# ledtiny85-nrf-sot23.net
KiCad netlist of a schematic drawn in EAGLE
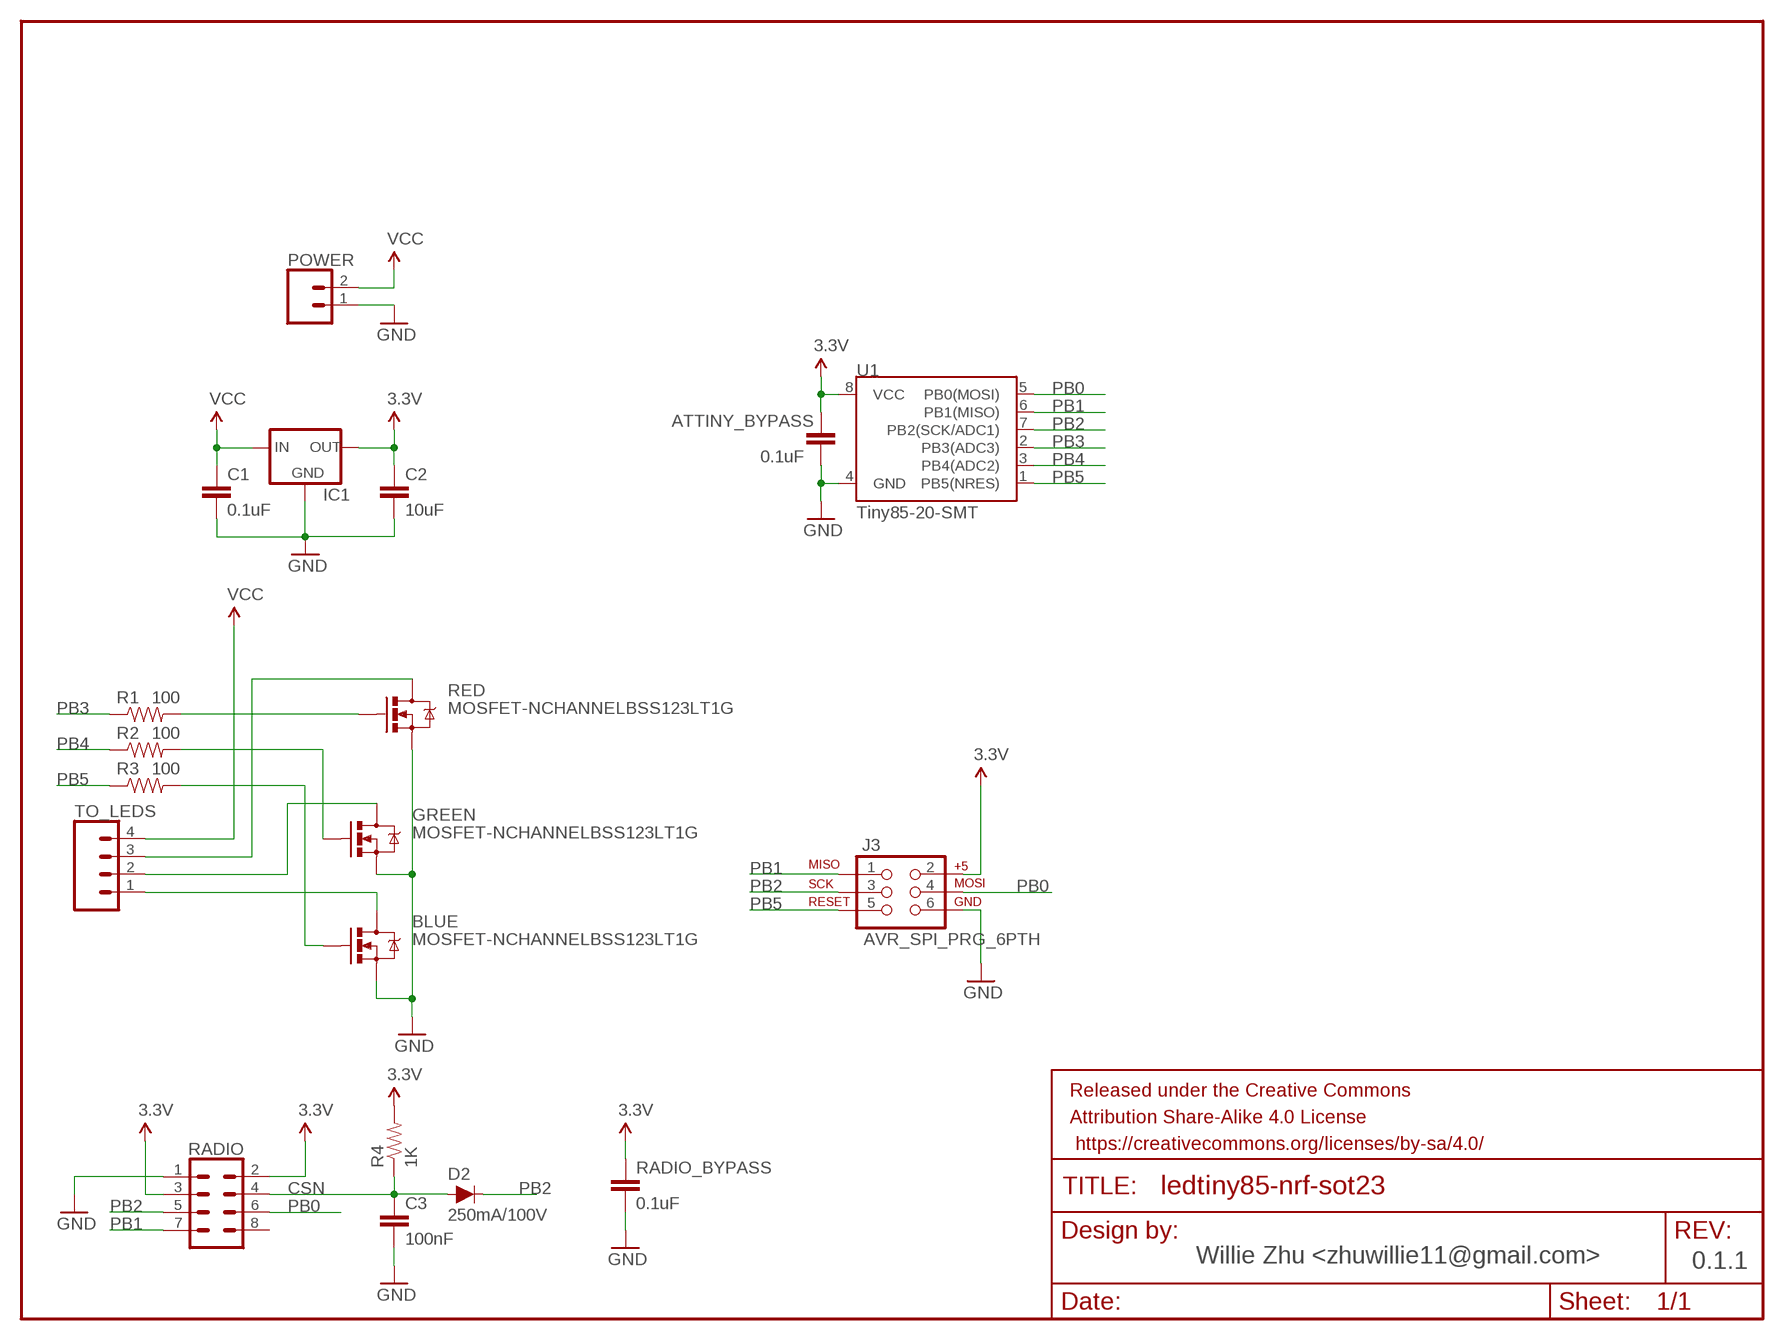
[diagram p0: schematic, sheet 1]

(export (version "E")
  (design (tool "Eeschema 10.0.6"))
  (components
    (comp (ref "ATTINY_BYPASS")
      (value "0.1uF")
      (footprint "eagle-import:0805")
      (libsource (lib "eagle-import") (part "CAP0805"))
    )
    (comp (ref "BLUE")
      (value "MOSFET-NCHANNELBSS123LT1G")
      (footprint "eagle-import:SOT23-3")
      (libsource (lib "eagle-import") (part "MOSFET-NCHANNELBSS123LT1G"))
    )
    (comp (ref "C1")
      (value "0.1uF")
      (footprint "eagle-import:0805")
      (libsource (lib "eagle-import") (part "CAP0805"))
    )
    (comp (ref "C2")
      (value "10uF")
      (footprint "eagle-import:0805")
      (libsource (lib "eagle-import") (part "CAP0805"))
    )
    (comp (ref "C3")
      (value "100nF")
      (footprint "eagle-import:0805")
      (libsource (lib "eagle-import") (part "CAP0805"))
    )
    (comp (ref "D2")
      (value "250mA/100V")
      (footprint "eagle-import:SOD-323")
      (libsource (lib "eagle-import") (part "DIODE-BAS16J"))
    )
    (comp (ref "FRAME1")
      (value "FRAME-LETTER")
      (footprint "eagle-import:CREATIVE_COMMONS")
      (libsource (lib "eagle-import") (part "FRAME-LETTER"))
    )
    (comp (ref "GREEN")
      (value "MOSFET-NCHANNELBSS123LT1G")
      (footprint "eagle-import:SOT23-3")
      (libsource (lib "eagle-import") (part "MOSFET-NCHANNELBSS123LT1G"))
    )
    (comp (ref "IC1")
      (value "XC63FPM")
      (footprint "eagle-import:SOT23")
      (libsource (lib "eagle-import") (part "XC63FPM"))
    )
    (comp (ref "J3")
      (value "AVR_SPI_PRG_6PTH")
      (footprint "eagle-import:2X3")
      (libsource (lib "eagle-import") (part "AVR_SPI_PRG_6PTH"))
    )
    (comp (ref "POWER")
      (value "CONN_02")
      (footprint "eagle-import:1X02")
      (libsource (lib "eagle-import") (part "CONN_02"))
    )
    (comp (ref "R1")
      (value "100")
      (footprint "eagle-import:0805")
      (libsource (lib "eagle-import") (part "RESISTOR0805"))
    )
    (comp (ref "R2")
      (value "100")
      (footprint "eagle-import:0805")
      (libsource (lib "eagle-import") (part "RESISTOR0805"))
    )
    (comp (ref "R3")
      (value "100")
      (footprint "eagle-import:0805")
      (libsource (lib "eagle-import") (part "RESISTOR0805"))
    )
    (comp (ref "R4")
      (value "1K")
      (footprint "eagle-import:0805")
      (libsource (lib "eagle-import") (part "RESISTOR0805-RES"))
    )
    (comp (ref "RADIO")
      (value "CONN_04X2")
      (footprint "eagle-import:2X4")
      (libsource (lib "eagle-import") (part "CONN_04X2"))
    )
    (comp (ref "RADIO_BYPASS")
      (value "0.1uF")
      (footprint "eagle-import:0805")
      (libsource (lib "eagle-import") (part "CAP0805"))
    )
    (comp (ref "RED")
      (value "MOSFET-NCHANNELBSS123LT1G")
      (footprint "eagle-import:SOT23-3")
      (libsource (lib "eagle-import") (part "MOSFET-NCHANNELBSS123LT1G"))
    )
    (comp (ref "TO_LEDS")
      (value "CONN_04")
      (footprint "eagle-import:1X04")
      (libsource (lib "eagle-import") (part "CONN_04"))
    )
    (comp (ref "U1")
      (value "Tiny85-20-SMT")
      (footprint "eagle-import:SO08-EIAJ")
      (libsource (lib "eagle-import") (part "ATTINY45TINY85-20-SMT"))
    )
  )
  (nets
    (net (code "1") (name "/CSN") (class "Default")
      (node (ref "C3") (pin "1") (pinfunction "1_1") (pintype "passive"))
      (node (ref "D2") (pin "A") (pinfunction "A_A") (pintype "passive"))
      (node (ref "R4") (pin "1") (pinfunction "1_1") (pintype "passive"))
      (node (ref "RADIO") (pin "4") (pinfunction "4_4") (pintype "passive"))
    )
    (net (code "2") (name "/PB0") (class "Default")
      (node (ref "J3") (pin "4") (pinfunction "4_4") (pintype "passive"))
      (node (ref "RADIO") (pin "6") (pinfunction "6_6") (pintype "passive"))
      (node (ref "U1") (pin "5") (pinfunction "PB0(MOSI)_5") (pintype "bidirectional"))
    )
    (net (code "3") (name "/PB1") (class "Default")
      (node (ref "J3") (pin "1") (pinfunction "1_1") (pintype "passive"))
      (node (ref "RADIO") (pin "7") (pinfunction "7_7") (pintype "passive"))
      (node (ref "U1") (pin "6") (pinfunction "PB1(MISO)_6") (pintype "bidirectional"))
    )
    (net (code "4") (name "/PB2") (class "Default")
      (node (ref "D2") (pin "C") (pinfunction "C_C") (pintype "passive"))
      (node (ref "J3") (pin "3") (pinfunction "3_3") (pintype "passive"))
      (node (ref "RADIO") (pin "5") (pinfunction "5_5") (pintype "passive"))
      (node (ref "U1") (pin "7") (pinfunction "PB2(SCK/ADC1)_7") (pintype "bidirectional"))
    )
    (net (code "5") (name "/PB3") (class "Default")
      (node (ref "R1") (pin "1") (pinfunction "1_1") (pintype "passive"))
      (node (ref "U1") (pin "2") (pinfunction "PB3(ADC3)_2") (pintype "bidirectional"))
    )
    (net (code "6") (name "/PB4") (class "Default")
      (node (ref "R2") (pin "1") (pinfunction "1_1") (pintype "passive"))
      (node (ref "U1") (pin "3") (pinfunction "PB4(ADC2)_3") (pintype "bidirectional"))
    )
    (net (code "7") (name "/PB5") (class "Default")
      (node (ref "J3") (pin "5") (pinfunction "5_5") (pintype "passive"))
      (node (ref "R3") (pin "1") (pinfunction "1_1") (pintype "passive"))
      (node (ref "U1") (pin "1") (pinfunction "PB5(NRES)_1") (pintype "bidirectional"))
    )
    (net (code "8") (name "3.3V") (class "Default")
      (node (ref "ATTINY_BYPASS") (pin "1") (pinfunction "1_1") (pintype "passive"))
      (node (ref "C2") (pin "1") (pinfunction "1_1") (pintype "passive"))
      (node (ref "IC1") (pin "2") (pinfunction "OUT_2") (pintype "passive"))
      (node (ref "J3") (pin "2") (pinfunction "2_2") (pintype "passive"))
      (node (ref "R4") (pin "2") (pinfunction "2_2") (pintype "passive"))
      (node (ref "RADIO") (pin "2") (pinfunction "2_2") (pintype "passive"))
      (node (ref "RADIO") (pin "3") (pinfunction "3_3") (pintype "passive"))
      (node (ref "RADIO_BYPASS") (pin "1") (pinfunction "1_1") (pintype "passive"))
      (node (ref "U1") (pin "8") (pinfunction "VCC_8") (pintype "bidirectional"))
    )
    (net (code "9") (name "GND") (class "Default")
      (node (ref "ATTINY_BYPASS") (pin "2") (pinfunction "2_2") (pintype "passive"))
      (node (ref "BLUE") (pin "2") (pinfunction "S_2") (pintype "passive"))
      (node (ref "C1") (pin "2") (pinfunction "2_2") (pintype "passive"))
      (node (ref "C2") (pin "2") (pinfunction "2_2") (pintype "passive"))
      (node (ref "C3") (pin "2") (pinfunction "2_2") (pintype "passive"))
      (node (ref "GREEN") (pin "2") (pinfunction "S_2") (pintype "passive"))
      (node (ref "IC1") (pin "1") (pinfunction "GND_1") (pintype "input"))
      (node (ref "J3") (pin "6") (pinfunction "6_6") (pintype "passive"))
      (node (ref "POWER") (pin "1") (pinfunction "1_1") (pintype "passive"))
      (node (ref "RADIO") (pin "1") (pinfunction "1_1") (pintype "passive"))
      (node (ref "RADIO_BYPASS") (pin "2") (pinfunction "2_2") (pintype "passive"))
      (node (ref "RED") (pin "2") (pinfunction "S_2") (pintype "passive"))
      (node (ref "U1") (pin "4") (pinfunction "GND_4") (pintype "bidirectional"))
    )
    (net (code "10") (name "Net-(BLUE-D)") (class "Default")
      (node (ref "BLUE") (pin "3") (pinfunction "D_3") (pintype "passive"))
      (node (ref "TO_LEDS") (pin "1") (pinfunction "1_1") (pintype "passive"))
    )
    (net (code "11") (name "Net-(BLUE-G)") (class "Default")
      (node (ref "BLUE") (pin "1") (pinfunction "G_1") (pintype "passive"))
      (node (ref "R3") (pin "2") (pinfunction "2_2") (pintype "passive"))
    )
    (net (code "12") (name "Net-(GREEN-D)") (class "Default")
      (node (ref "GREEN") (pin "3") (pinfunction "D_3") (pintype "passive"))
      (node (ref "TO_LEDS") (pin "2") (pinfunction "2_2") (pintype "passive"))
    )
    (net (code "13") (name "Net-(GREEN-G)") (class "Default")
      (node (ref "GREEN") (pin "1") (pinfunction "G_1") (pintype "passive"))
      (node (ref "R2") (pin "2") (pinfunction "2_2") (pintype "passive"))
    )
    (net (code "14") (name "Net-(RED-D)") (class "Default")
      (node (ref "RED") (pin "3") (pinfunction "D_3") (pintype "passive"))
      (node (ref "TO_LEDS") (pin "3") (pinfunction "3_3") (pintype "passive"))
    )
    (net (code "15") (name "Net-(RED-G)") (class "Default")
      (node (ref "R1") (pin "2") (pinfunction "2_2") (pintype "passive"))
      (node (ref "RED") (pin "1") (pinfunction "G_1") (pintype "passive"))
    )
    (net (code "16") (name "VCC") (class "Default")
      (node (ref "C1") (pin "1") (pinfunction "1_1") (pintype "passive"))
      (node (ref "IC1") (pin "3") (pinfunction "IN_3") (pintype "input"))
      (node (ref "POWER") (pin "2") (pinfunction "2_2") (pintype "passive"))
      (node (ref "TO_LEDS") (pin "4") (pinfunction "4_4") (pintype "passive"))
    )
    (net (code "17") (name "unconnected-(RADIO-Pad8)") (class "Default")
      (node (ref "RADIO") (pin "8") (pinfunction "8_8") (pintype "passive"))
    )
  )
)
